# A-skin.net
KiCad netlist of a schematic drawn in EasyEDA
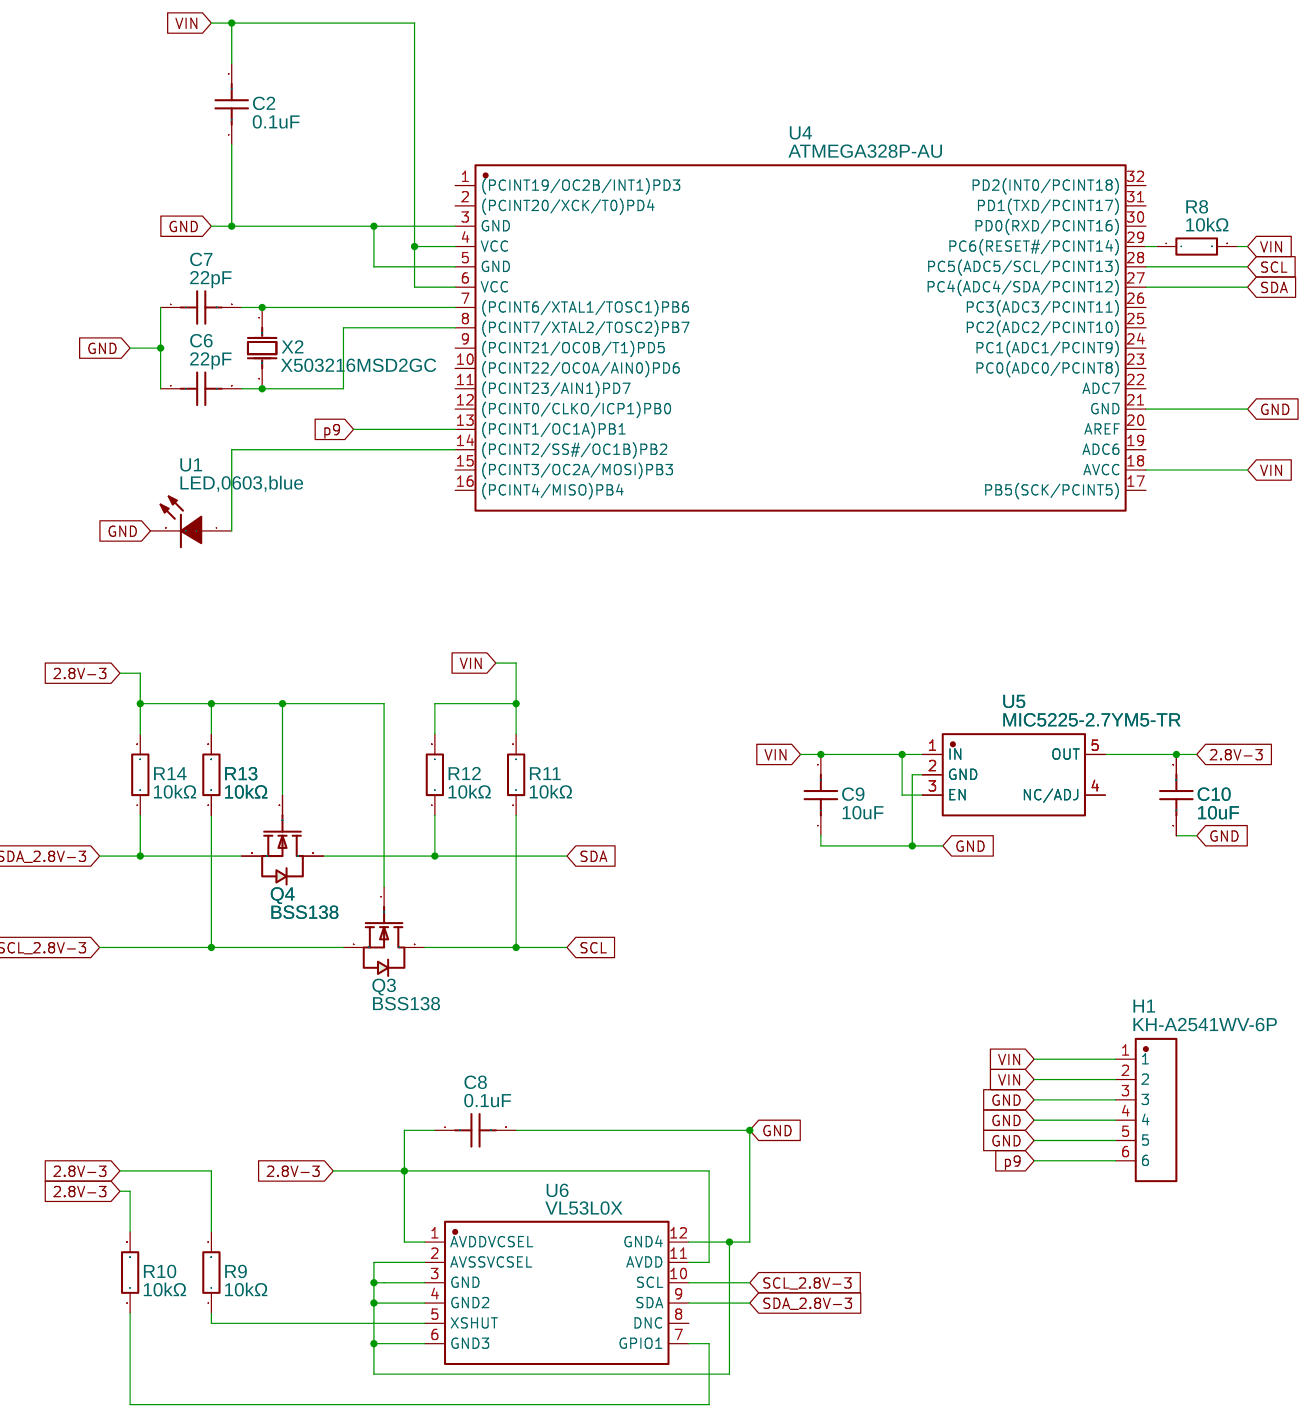
[diagram p0: schematic sheet]

(export (version "E")
  (design (tool "Eeschema 10.0.6"))
  (components
    (comp (ref "C2")
      (value "0.1uF")
      (fields
        (field (name "BOM_Manufacturer Part") "0603BB104K500NGT")
        (field (name "BOM_Supplier Part") "C2168571")
      )
      (libsource (lib "") (part "0603BB104K500NGT_1"))
    )
    (comp (ref "C6")
      (value "22pF")
      (fields
        (field (name "BOM_Manufacturer Part") "C0603C220J5GACAUTO")
        (field (name "BOM_Supplier Part") "C599692")
      )
      (libsource (lib "") (part "C0603C220J5GACAUTO"))
    )
    (comp (ref "C7")
      (value "22pF")
      (fields
        (field (name "BOM_Manufacturer Part") "C0603C220J5GACAUTO")
        (field (name "BOM_Supplier Part") "C599692")
      )
      (libsource (lib "") (part "C0603C220J5GACAUTO"))
    )
    (comp (ref "C8")
      (value "0.1uF")
      (fields
        (field (name "BOM_Manufacturer Part") "0603BB104K500NGT")
        (field (name "BOM_Supplier Part") "C2168571")
      )
      (libsource (lib "") (part "0603BB104K500NGT"))
    )
    (comp (ref "C9")
      (value "10uF")
      (fields
        (field (name "BOM_Manufacturer Part") "GRM21BR71A106KA73L")
        (field (name "BOM_Supplier Part") "C117956")
      )
      (libsource (lib "") (part "GRM21BR71A106KA73L"))
    )
    (comp (ref "C10")
      (value "10uF")
      (fields
        (field (name "BOM_Manufacturer Part") "GRM21BR71A106KA73L")
        (field (name "BOM_Supplier Part") "C117956")
      )
      (libsource (lib "") (part "GRM21BR71A106KA73L"))
    )
    (comp (ref "H1")
      (value "KH-A2541WV-6P")
      (fields (field (name "BOM_Supplier Part") "C2833331"))
      (libsource (lib "") (part "KH-A2541WV-6P"))
    )
    (comp (ref "Q3")
      (value "BSS138")
      (fields (field (name "BOM_Supplier Part") "C78284"))
      (libsource (lib "") (part "BSS138"))
    )
    (comp (ref "Q4")
      (value "BSS138")
      (fields (field (name "BOM_Supplier Part") "C78284"))
      (libsource (lib "") (part "BSS138"))
    )
    (comp (ref "R8")
      (value "10kΩ")
      (fields
        (field (name "BOM_Manufacturer Part") "ETCR0603F10K0K9")
        (field (name "BOM_Supplier Part") "C365375")
      )
      (libsource (lib "") (part "ETCR0603F10K0K9_1"))
    )
    (comp (ref "R9")
      (value "10kΩ")
      (fields
        (field (name "BOM_Manufacturer Part") "ETCR0603F10K0K9")
        (field (name "BOM_Supplier Part") "C365375")
      )
      (libsource (lib "") (part "ETCR0603F10K0K9"))
    )
    (comp (ref "R10")
      (value "10kΩ")
      (fields
        (field (name "BOM_Manufacturer Part") "ETCR0603F10K0K9")
        (field (name "BOM_Supplier Part") "C365375")
      )
      (libsource (lib "") (part "ETCR0603F10K0K9"))
    )
    (comp (ref "R11")
      (value "10kΩ")
      (fields
        (field (name "BOM_Manufacturer Part") "ETCR0603F10K0K9")
        (field (name "BOM_Supplier Part") "C365375")
      )
      (libsource (lib "") (part "ETCR0603F10K0K9"))
    )
    (comp (ref "R12")
      (value "10kΩ")
      (fields
        (field (name "BOM_Manufacturer Part") "ETCR0603F10K0K9")
        (field (name "BOM_Supplier Part") "C365375")
      )
      (libsource (lib "") (part "ETCR0603F10K0K9"))
    )
    (comp (ref "R13")
      (value "10kΩ")
      (fields
        (field (name "BOM_Manufacturer Part") "ETCR0603F10K0K9")
        (field (name "BOM_Supplier Part") "C365375")
      )
      (libsource (lib "") (part "ETCR0603F10K0K9"))
    )
    (comp (ref "R14")
      (value "10kΩ")
      (fields
        (field (name "BOM_Manufacturer Part") "ETCR0603F10K0K9")
        (field (name "BOM_Supplier Part") "C365375")
      )
      (libsource (lib "") (part "ETCR0603F10K0K9"))
    )
    (comp (ref "U1")
      (value "LED,0603,blue")
      (fields (field (name "Manufacturer Part") "LED灯,0603,蓝色"))
      (libsource (lib "") (part "LED灯,0603,蓝色"))
    )
    (comp (ref "U4")
      (value "ATMEGA328P-AU")
      (fields (field (name "BOM_Supplier Part") "C14877"))
      (libsource (lib "") (part "ATMEGA328P-AU"))
    )
    (comp (ref "U5")
      (value "MIC5225-2.7YM5-TR")
      (fields (field (name "BOM_Supplier Part") "C625863"))
      (libsource (lib "") (part "MIC5225-2.7YM5-TR"))
    )
    (comp (ref "U6")
      (value "VL53L0X")
      (fields (field (name "BOM_Supplier Part") "C2929940"))
      (libsource (lib "") (part "VL53L0X"))
    )
    (comp (ref "X2")
      (value "X503216MSD2GC")
      (fields (field (name "BOM_Supplier Part") "C49231"))
      (libsource (lib "") (part "X503216MSD2GC"))
    )
  )
  (nets
    (net (code "1") (name "2.8V-3") (class "Default")
      (node (ref "C10") (pin "2") (pinfunction "2_2") (pintype "unspecified"))
      (node (ref "C8") (pin "1") (pinfunction "1_1") (pintype "unspecified"))
      (node (ref "Q3") (pin "1") (pinfunction "G_1") (pintype "unspecified"))
      (node (ref "Q4") (pin "1") (pinfunction "G_1") (pintype "unspecified"))
      (node (ref "R10") (pin "2") (pinfunction "2_2") (pintype "unspecified"))
      (node (ref "R13") (pin "2") (pinfunction "2_2") (pintype "unspecified"))
      (node (ref "R14") (pin "2") (pinfunction "2_2") (pintype "unspecified"))
      (node (ref "R9") (pin "2") (pinfunction "2_2") (pintype "unspecified"))
      (node (ref "U5") (pin "5") (pinfunction "OUT_5") (pintype "unspecified"))
      (node (ref "U6") (pin "1") (pinfunction "AVDDVCSEL_1") (pintype "unspecified"))
      (node (ref "U6") (pin "11") (pinfunction "AVDD_11") (pintype "unspecified"))
    )
    (net (code "2") (name "GND") (class "Default")
      (node (ref "C10") (pin "1") (pinfunction "1_1") (pintype "unspecified"))
      (node (ref "C2") (pin "1") (pinfunction "1_1") (pintype "unspecified"))
      (node (ref "C6") (pin "1") (pinfunction "1_1") (pintype "unspecified"))
      (node (ref "C7") (pin "1") (pinfunction "1_1") (pintype "unspecified"))
      (node (ref "C8") (pin "2") (pinfunction "2_2") (pintype "unspecified"))
      (node (ref "C9") (pin "1") (pinfunction "1_1") (pintype "unspecified"))
      (node (ref "H1") (pin "3") (pinfunction "3_3") (pintype "unspecified"))
      (node (ref "H1") (pin "4") (pinfunction "4_4") (pintype "unspecified"))
      (node (ref "H1") (pin "5") (pinfunction "5_5") (pintype "unspecified"))
      (node (ref "U1") (pin "2") (pinfunction "K_2") (pintype "unspecified"))
      (node (ref "U4") (pin "21") (pinfunction "GND_21") (pintype "unspecified"))
      (node (ref "U4") (pin "3") (pinfunction "GND_3") (pintype "unspecified"))
      (node (ref "U4") (pin "5") (pinfunction "GND_5") (pintype "unspecified"))
      (node (ref "U5") (pin "2") (pinfunction "GND_2") (pintype "unspecified"))
      (node (ref "U6") (pin "12") (pinfunction "GND4_12") (pintype "unspecified"))
      (node (ref "U6") (pin "2") (pinfunction "AVSSVCSEL_2") (pintype "unspecified"))
      (node (ref "U6") (pin "3") (pinfunction "GND_3") (pintype "unspecified"))
      (node (ref "U6") (pin "4") (pinfunction "GND2_4") (pintype "unspecified"))
      (node (ref "U6") (pin "6") (pinfunction "GND3_6") (pintype "unspecified"))
    )
    (net (code "3") (name "Net-(U1-A)") (class "Default")
      (node (ref "U1") (pin "1") (pinfunction "A_1") (pintype "unspecified"))
      (node (ref "U4") (pin "14") (pinfunction "(PCINT2/SS#/OC1B)PB2_14") (pintype "unspecified"))
    )
    (net (code "4") (name "Net-(U4-(PCINT6{slash}XTAL1{slash}TOSC1)PB6)") (class "Default")
      (node (ref "C7") (pin "2") (pinfunction "2_2") (pintype "unspecified"))
      (node (ref "U4") (pin "7") (pinfunction "(PCINT6/XTAL1/TOSC1)PB6_7") (pintype "unspecified"))
      (node (ref "X2") (pin "1") (pinfunction "OSC1_1") (pintype "input"))
    )
    (net (code "5") (name "Net-(U4-(PCINT7{slash}XTAL2{slash}TOSC2)PB7)") (class "Default")
      (node (ref "C6") (pin "2") (pinfunction "2_2") (pintype "unspecified"))
      (node (ref "U4") (pin "8") (pinfunction "(PCINT7/XTAL2/TOSC2)PB7_8") (pintype "unspecified"))
      (node (ref "X2") (pin "2") (pinfunction "OSC2_2") (pintype "input"))
    )
    (net (code "6") (name "Net-(U4-PC6(RESET#{slash}PCINT14))") (class "Default")
      (node (ref "R8") (pin "1") (pinfunction "1_1") (pintype "unspecified"))
      (node (ref "U4") (pin "29") (pinfunction "PC6(RESET#/PCINT14)_29") (pintype "unspecified"))
    )
    (net (code "7") (name "Net-(U6-GPIO1)") (class "Default")
      (node (ref "R10") (pin "1") (pinfunction "1_1") (pintype "unspecified"))
      (node (ref "U6") (pin "7") (pinfunction "GPIO1_7") (pintype "unspecified"))
    )
    (net (code "8") (name "Net-(U6-XSHUT)") (class "Default")
      (node (ref "R9") (pin "1") (pinfunction "1_1") (pintype "unspecified"))
      (node (ref "U6") (pin "5") (pinfunction "XSHUT_5") (pintype "unspecified"))
    )
    (net (code "9") (name "SCL") (class "Default")
      (node (ref "Q3") (pin "3") (pinfunction "D_3") (pintype "unspecified"))
      (node (ref "R11") (pin "1") (pinfunction "1_1") (pintype "unspecified"))
      (node (ref "U4") (pin "28") (pinfunction "PC5(ADC5/SCL/PCINT13)_28") (pintype "unspecified"))
    )
    (net (code "10") (name "SCL_2.8V-3") (class "Default")
      (node (ref "Q3") (pin "2") (pinfunction "S_2") (pintype "unspecified"))
      (node (ref "R13") (pin "1") (pinfunction "1_1") (pintype "unspecified"))
      (node (ref "U6") (pin "10") (pinfunction "SCL_10") (pintype "unspecified"))
    )
    (net (code "11") (name "SDA") (class "Default")
      (node (ref "Q4") (pin "3") (pinfunction "D_3") (pintype "unspecified"))
      (node (ref "R12") (pin "1") (pinfunction "1_1") (pintype "unspecified"))
      (node (ref "U4") (pin "27") (pinfunction "PC4(ADC4/SDA/PCINT12)_27") (pintype "unspecified"))
    )
    (net (code "12") (name "SDA_2.8V-3") (class "Default")
      (node (ref "Q4") (pin "2") (pinfunction "S_2") (pintype "unspecified"))
      (node (ref "R14") (pin "1") (pinfunction "1_1") (pintype "unspecified"))
      (node (ref "U6") (pin "9") (pinfunction "SDA_9") (pintype "unspecified"))
    )
    (net (code "13") (name "VIN") (class "Default")
      (node (ref "C2") (pin "2") (pinfunction "2_2") (pintype "unspecified"))
      (node (ref "C9") (pin "2") (pinfunction "2_2") (pintype "unspecified"))
      (node (ref "H1") (pin "1") (pinfunction "1_1") (pintype "unspecified"))
      (node (ref "H1") (pin "2") (pinfunction "2_2") (pintype "unspecified"))
      (node (ref "R11") (pin "2") (pinfunction "2_2") (pintype "unspecified"))
      (node (ref "R12") (pin "2") (pinfunction "2_2") (pintype "unspecified"))
      (node (ref "R8") (pin "2") (pinfunction "2_2") (pintype "unspecified"))
      (node (ref "U4") (pin "18") (pinfunction "AVCC_18") (pintype "unspecified"))
      (node (ref "U4") (pin "4") (pinfunction "VCC_4") (pintype "unspecified"))
      (node (ref "U4") (pin "6") (pinfunction "VCC_6") (pintype "unspecified"))
      (node (ref "U5") (pin "1") (pinfunction "IN_1") (pintype "unspecified"))
      (node (ref "U5") (pin "3") (pinfunction "EN_3") (pintype "unspecified"))
    )
    (net (code "14") (name "p9") (class "Default")
      (node (ref "H1") (pin "6") (pinfunction "6_6") (pintype "unspecified"))
      (node (ref "U4") (pin "13") (pinfunction "(PCINT1/OC1A)PB1_13") (pintype "unspecified"))
    )
    (net (code "15") (name "unconnected-(U4-(PCINT0{slash}CLKO{slash}ICP1)PB0-Pad12)") (class "Default")
      (node (ref "U4") (pin "12") (pinfunction "(PCINT0/CLKO/ICP1)PB0_12") (pintype "unspecified"))
    )
    (net (code "16") (name "unconnected-(U4-(PCINT3{slash}OC2A{slash}MOSI)PB3-Pad15)") (class "Default")
      (node (ref "U4") (pin "15") (pinfunction "(PCINT3/OC2A/MOSI)PB3_15") (pintype "unspecified"))
    )
    (net (code "17") (name "unconnected-(U4-(PCINT4{slash}MISO)PB4-Pad16)") (class "Default")
      (node (ref "U4") (pin "16") (pinfunction "(PCINT4/MISO)PB4_16") (pintype "unspecified"))
    )
    (net (code "18") (name "unconnected-(U4-(PCINT19{slash}OC2B{slash}INT1)PD3-Pad1)") (class "Default")
      (node (ref "U4") (pin "1") (pinfunction "(PCINT19/OC2B/INT1)PD3_1") (pintype "unspecified"))
    )
    (net (code "19") (name "unconnected-(U4-(PCINT20{slash}XCK{slash}T0)PD4-Pad2)") (class "Default")
      (node (ref "U4") (pin "2") (pinfunction "(PCINT20/XCK/T0)PD4_2") (pintype "unspecified"))
    )
    (net (code "20") (name "unconnected-(U4-(PCINT21{slash}OC0B{slash}T1)PD5-Pad9)") (class "Default")
      (node (ref "U4") (pin "9") (pinfunction "(PCINT21/OC0B/T1)PD5_9") (pintype "unspecified"))
    )
    (net (code "21") (name "unconnected-(U4-(PCINT22{slash}OC0A{slash}AIN0)PD6-Pad10)") (class "Default")
      (node (ref "U4") (pin "10") (pinfunction "(PCINT22/OC0A/AIN0)PD6_10") (pintype "unspecified"))
    )
    (net (code "22") (name "unconnected-(U4-(PCINT23{slash}AIN1)PD7-Pad11)") (class "Default")
      (node (ref "U4") (pin "11") (pinfunction "(PCINT23/AIN1)PD7_11") (pintype "unspecified"))
    )
    (net (code "23") (name "unconnected-(U4-ADC6-Pad19)") (class "Default")
      (node (ref "U4") (pin "19") (pinfunction "ADC6_19") (pintype "unspecified"))
    )
    (net (code "24") (name "unconnected-(U4-ADC7-Pad22)") (class "Default")
      (node (ref "U4") (pin "22") (pinfunction "ADC7_22") (pintype "unspecified"))
    )
    (net (code "25") (name "unconnected-(U4-AREF-Pad20)") (class "Default")
      (node (ref "U4") (pin "20") (pinfunction "AREF_20") (pintype "unspecified"))
    )
    (net (code "26") (name "unconnected-(U4-PB5(SCK{slash}PCINT5)-Pad17)") (class "Default")
      (node (ref "U4") (pin "17") (pinfunction "PB5(SCK/PCINT5)_17") (pintype "unspecified"))
    )
    (net (code "27") (name "unconnected-(U4-PC0(ADC0{slash}PCINT8)-Pad23)") (class "Default")
      (node (ref "U4") (pin "23") (pinfunction "PC0(ADC0/PCINT8)_23") (pintype "unspecified"))
    )
    (net (code "28") (name "unconnected-(U4-PC1(ADC1{slash}PCINT9)-Pad24)") (class "Default")
      (node (ref "U4") (pin "24") (pinfunction "PC1(ADC1/PCINT9)_24") (pintype "unspecified"))
    )
    (net (code "29") (name "unconnected-(U4-PC2(ADC2{slash}PCINT10)-Pad25)") (class "Default")
      (node (ref "U4") (pin "25") (pinfunction "PC2(ADC2/PCINT10)_25") (pintype "unspecified"))
    )
    (net (code "30") (name "unconnected-(U4-PC3(ADC3{slash}PCINT11)-Pad26)") (class "Default")
      (node (ref "U4") (pin "26") (pinfunction "PC3(ADC3/PCINT11)_26") (pintype "unspecified"))
    )
    (net (code "31") (name "unconnected-(U4-PD0(RXD{slash}PCINT16)-Pad30)") (class "Default")
      (node (ref "U4") (pin "30") (pinfunction "PD0(RXD/PCINT16)_30") (pintype "unspecified"))
    )
    (net (code "32") (name "unconnected-(U4-PD1(TXD{slash}PCINT17)-Pad31)") (class "Default")
      (node (ref "U4") (pin "31") (pinfunction "PD1(TXD/PCINT17)_31") (pintype "unspecified"))
    )
    (net (code "33") (name "unconnected-(U4-PD2(INT0{slash}PCINT18)-Pad32)") (class "Default")
      (node (ref "U4") (pin "32") (pinfunction "PD2(INT0/PCINT18)_32") (pintype "unspecified"))
    )
    (net (code "34") (name "unconnected-(U5-NC{slash}ADJ-Pad4)") (class "Default")
      (node (ref "U5") (pin "4") (pinfunction "NC/ADJ_4") (pintype "unspecified"))
    )
    (net (code "35") (name "unconnected-(U6-DNC-Pad8)") (class "Default")
      (node (ref "U6") (pin "8") (pinfunction "DNC_8") (pintype "unspecified"))
    )
  )
)
